# tia-rev1.net
KiCad netlist of a schematic drawn in EAGLE
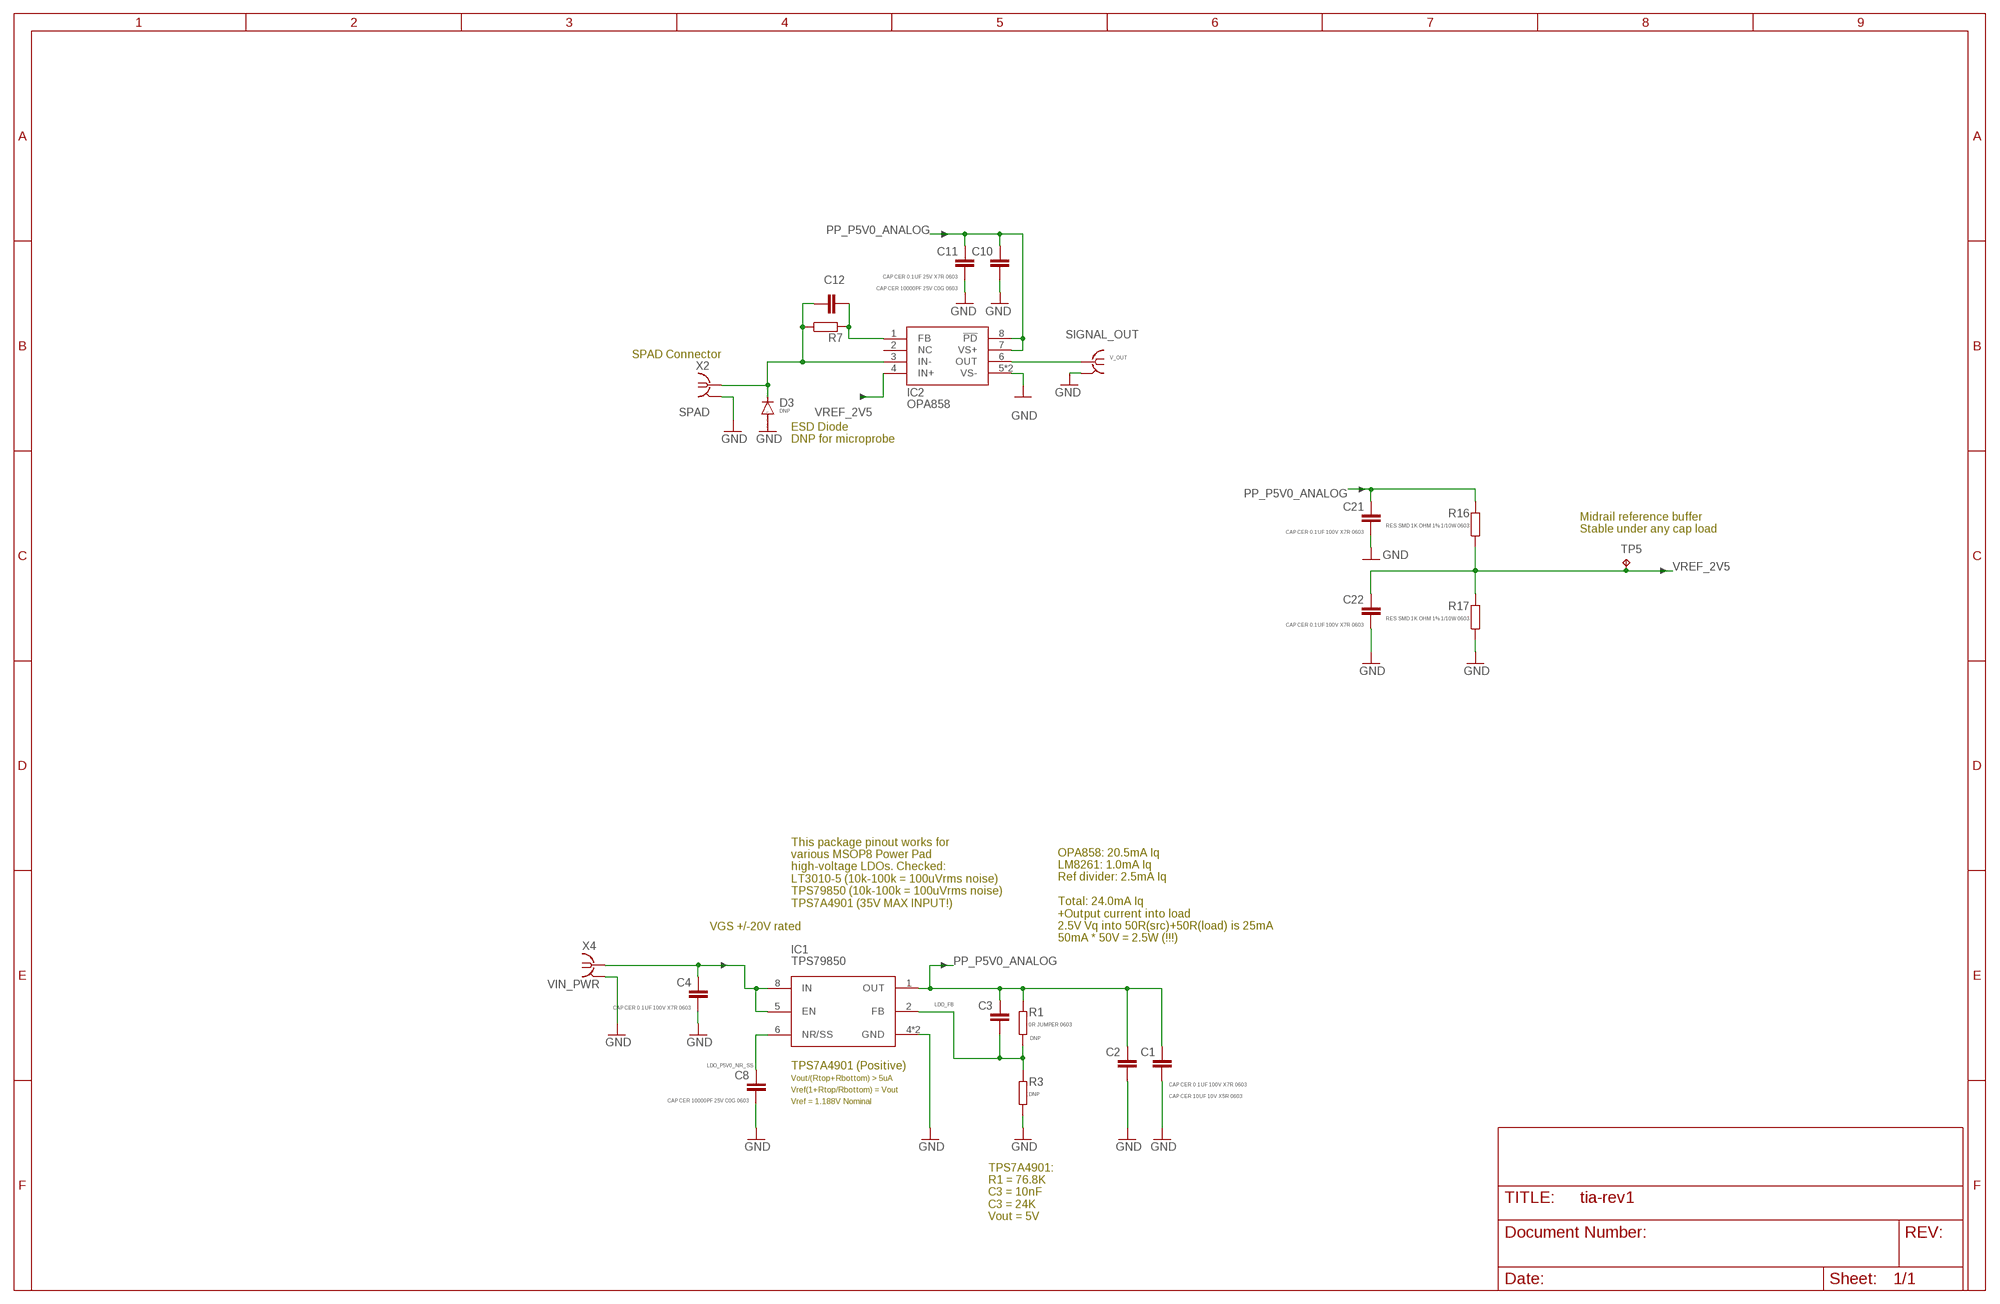
[diagram p0: schematic, sheet 1]

(export (version "E")
  (design (tool "Eeschema 10.0.6"))
  (components
    (comp (ref "C1")
      (value "CAP CER 10UF 10V X5R 0603")
      (footprint "eagle-import:C0603")
      (libsource (lib "eagle-import") (part "C-EUC0603"))
    )
    (comp (ref "C2")
      (value "CAP CER 0.1UF 100V X7R 0603")
      (footprint "eagle-import:C0603")
      (libsource (lib "eagle-import") (part "C-EUC0603"))
    )
    (comp (ref "C3")
      (value "DNP")
      (footprint "eagle-import:C0603")
      (libsource (lib "eagle-import") (part "C-EUC0603"))
    )
    (comp (ref "C4")
      (value "CAP CER 0.1UF 100V X7R 0603")
      (footprint "eagle-import:C0603")
      (libsource (lib "eagle-import") (part "C-EUC0603"))
    )
    (comp (ref "C8")
      (value "CAP CER 10000PF 25V C0G 0603")
      (footprint "eagle-import:C0603")
      (libsource (lib "eagle-import") (part "C-EUC0603"))
    )
    (comp (ref "C10")
      (value "CAP CER 10000PF 25V C0G 0603")
      (footprint "eagle-import:C0603")
      (libsource (lib "eagle-import") (part "C-EUC0603"))
    )
    (comp (ref "C11")
      (value "CAP CER 0.1UF 25V X7R 0603")
      (footprint "eagle-import:C0603")
      (libsource (lib "eagle-import") (part "C-EUC0603"))
    )
    (comp (ref "C12")
      (value "CAP CER 0.1UF 25V X7R 0603")
      (footprint "eagle-import:C0603")
      (libsource (lib "eagle-import") (part "C-EUC0603"))
    )
    (comp (ref "C21")
      (value "CAP CER 0.1UF 100V X7R 0603")
      (footprint "eagle-import:C0603")
      (libsource (lib "eagle-import") (part "C-EUC0603"))
    )
    (comp (ref "C22")
      (value "CAP CER 0.1UF 100V X7R 0603")
      (footprint "eagle-import:C0603")
      (libsource (lib "eagle-import") (part "C-EUC0603"))
    )
    (comp (ref "D3")
      (value "DNP")
      (footprint "eagle-import:SOD323-W")
      (libsource (lib "eagle-import") (part "DIODE-SOD323-W"))
    )
    (comp (ref "IC1")
      (value "TPS79850")
      (footprint "eagle-import:MSOP-8_POWER_PAD")
      (libsource (lib "eagle-import") (part "TPS7A"))
    )
    (comp (ref "IC2")
      (value "OPA858")
      (footprint "eagle-import:WSON8")
      (libsource (lib "eagle-import") (part "OPA858"))
    )
    (comp (ref "R1")
      (value "0R JUMPER 0603")
      (footprint "eagle-import:R0603")
      (libsource (lib "eagle-import") (part "R-EU_R0603"))
    )
    (comp (ref "R3")
      (value "DNP")
      (footprint "eagle-import:R0603")
      (libsource (lib "eagle-import") (part "R-EU_R0603"))
    )
    (comp (ref "R7")
      (value "DNP")
      (footprint "eagle-import:R0603")
      (libsource (lib "eagle-import") (part "R-EU_R0603"))
    )
    (comp (ref "R16")
      (value "RES SMD 1K OHM 1% 1/10W 0603")
      (footprint "eagle-import:R0603")
      (libsource (lib "eagle-import") (part "R-EU_R0603"))
    )
    (comp (ref "R17")
      (value "RES SMD 1K OHM 1% 1/10W 0603")
      (footprint "eagle-import:R0603")
      (libsource (lib "eagle-import") (part "R-EU_R0603"))
    )
    (comp (ref "TP5")
      (value "TPTP10R")
      (footprint "eagle-import:TP10R")
      (libsource (lib "eagle-import") (part "TPTP10R"))
    )
    (comp (ref "X2")
      (value "SPAD")
      (footprint "eagle-import:J502-ND-142-0701-881_886")
      (fields (field (name "MF") "JOHNSON COMPONENTS") (field (name "MPN") "142-0701-881"))
      (libsource (lib "eagle-import") (part "SMA-142-0701-881/886"))
    )
    (comp (ref "X3")
      (value "SIGNAL_OUT")
      (footprint "eagle-import:MMCX-J-P-X-ST-EM1-MKT")
      (fields (field (name "MF") "Samtec Inc.") (field (name "MPN") "MMCX-J-P-X-ST-EM1-MKT"))
      (libsource (lib "eagle-import") (part "COAX"))
    )
    (comp (ref "X4")
      (value "VIN_PWR")
      (footprint "eagle-import:MMCX-J-P-X-ST-EM1-MKT")
      (fields (field (name "MF") "Samtec Inc.") (field (name "MPN") "MMCX-J-P-X-ST-EM1-MKT"))
      (libsource (lib "eagle-import") (part "COAX"))
    )
  )
  (nets
    (net (code "1") (name "/LDO_FB") (class "Default")
      (node (ref "C3") (pin "2") (pinfunction "2_2") (pintype "passive"))
      (node (ref "IC1") (pin "2") (pinfunction "FB_2") (pintype "bidirectional"))
      (node (ref "R1") (pin "1") (pinfunction "1_1") (pintype "passive"))
      (node (ref "R3") (pin "1") (pinfunction "1_1") (pintype "passive"))
    )
    (net (code "2") (name "/LDO_P5V0_NR_SS") (class "Default")
      (node (ref "C8") (pin "1") (pinfunction "1_1") (pintype "passive"))
      (node (ref "IC1") (pin "6") (pinfunction "NR/SS_6") (pintype "bidirectional"))
    )
    (net (code "3") (name "/PP_P5V0_ANALOG") (class "Default")
      (node (ref "C1") (pin "1") (pinfunction "1_1") (pintype "passive"))
      (node (ref "C10") (pin "1") (pinfunction "1_1") (pintype "passive"))
      (node (ref "C11") (pin "1") (pinfunction "1_1") (pintype "passive"))
      (node (ref "C2") (pin "1") (pinfunction "1_1") (pintype "passive"))
      (node (ref "C21") (pin "1") (pinfunction "1_1") (pintype "passive"))
      (node (ref "C3") (pin "1") (pinfunction "1_1") (pintype "passive"))
      (node (ref "IC1") (pin "1") (pinfunction "OUT_1") (pintype "bidirectional"))
      (node (ref "IC2") (pin "7") (pinfunction "VS+_7") (pintype "bidirectional"))
      (node (ref "IC2") (pin "8") (pinfunction "~{PD}_8") (pintype "bidirectional"))
      (node (ref "R1") (pin "2") (pinfunction "2_2") (pintype "passive"))
      (node (ref "R16") (pin "2") (pinfunction "2_2") (pintype "passive"))
    )
    (net (code "4") (name "/VREF_2V5") (class "Default")
      (node (ref "C22") (pin "1") (pinfunction "1_1") (pintype "passive"))
      (node (ref "R16") (pin "1") (pinfunction "1_1") (pintype "passive"))
      (node (ref "R17") (pin "2") (pinfunction "2_2") (pintype "passive"))
      (node (ref "TP5") (pin "TP") (pinfunction "TP_TP") (pintype "input"))
    )
    (net (code "5") (name "/V_OUT") (class "Default")
      (node (ref "IC2") (pin "6") (pinfunction "OUT_6") (pintype "bidirectional"))
      (node (ref "X3") (pin "1") (pinfunction "1_1") (pintype "passive"))
    )
    (net (code "6") (name "GND") (class "Default")
      (node (ref "C1") (pin "2") (pinfunction "2_2") (pintype "passive"))
      (node (ref "C10") (pin "2") (pinfunction "2_2") (pintype "passive"))
      (node (ref "C11") (pin "2") (pinfunction "2_2") (pintype "passive"))
      (node (ref "C2") (pin "2") (pinfunction "2_2") (pintype "passive"))
      (node (ref "C21") (pin "2") (pinfunction "2_2") (pintype "passive"))
      (node (ref "C22") (pin "2") (pinfunction "2_2") (pintype "passive"))
      (node (ref "C4") (pin "2") (pinfunction "2_2") (pintype "passive"))
      (node (ref "C8") (pin "2") (pinfunction "2_2") (pintype "passive"))
      (node (ref "D3") (pin "A") (pinfunction "A_A") (pintype "passive"))
      (node (ref "IC1") (pin "4") (pinfunction "GND_4") (pintype "bidirectional"))
      (node (ref "IC1") (pin "PAD") (pinfunction "GND_PAD") (pintype "bidirectional"))
      (node (ref "IC2") (pin "5") (pinfunction "VS-_5") (pintype "bidirectional"))
      (node (ref "IC2") (pin "PAD") (pinfunction "VS-_PAD") (pintype "bidirectional"))
      (node (ref "R17") (pin "1") (pinfunction "1_1") (pintype "passive"))
      (node (ref "R3") (pin "2") (pinfunction "2_2") (pintype "passive"))
      (node (ref "X2") (pin "G@1") (pinfunction "GND_G@1") (pintype "power_in"))
      (node (ref "X3") (pin "2@1") (pinfunction "GND_2@1") (pintype "power_in"))
      (node (ref "X4") (pin "2@1") (pinfunction "GND_2@1") (pintype "power_in"))
    )
    (net (code "7") (name "Net-(IC1-EN)") (class "Default")
      (node (ref "C4") (pin "1") (pinfunction "1_1") (pintype "passive"))
      (node (ref "IC1") (pin "5") (pinfunction "EN_5") (pintype "bidirectional"))
      (node (ref "IC1") (pin "8") (pinfunction "IN_8") (pintype "bidirectional"))
      (node (ref "X4") (pin "1") (pinfunction "1_1") (pintype "passive"))
    )
    (net (code "8") (name "Net-(IC2-FB)") (class "Default")
      (node (ref "C12") (pin "2") (pinfunction "2_2") (pintype "passive"))
      (node (ref "IC2") (pin "1") (pinfunction "FB_1") (pintype "bidirectional"))
      (node (ref "R7") (pin "2") (pinfunction "2_2") (pintype "passive"))
    )
    (net (code "9") (name "Net-(IC2-IN-)") (class "Default")
      (node (ref "C12") (pin "1") (pinfunction "1_1") (pintype "passive"))
      (node (ref "D3") (pin "C") (pinfunction "C_C") (pintype "passive"))
      (node (ref "IC2") (pin "3") (pinfunction "IN-_3") (pintype "bidirectional"))
      (node (ref "R7") (pin "1") (pinfunction "1_1") (pintype "passive"))
      (node (ref "X2") (pin "1") (pinfunction "1_1") (pintype "passive"))
    )
    (net (code "10") (name "unconnected-(IC2-IN+-Pad4)") (class "Default")
      (node (ref "IC2") (pin "4") (pinfunction "IN+_4") (pintype "bidirectional"))
    )
    (net (code "11") (name "unconnected-(IC2-NC-Pad2)") (class "Default")
      (node (ref "IC2") (pin "2") (pinfunction "NC_2") (pintype "bidirectional"))
    )
  )
)
